# Sheet-new.net
KiCad netlist of a schematic drawn in Altium Designer
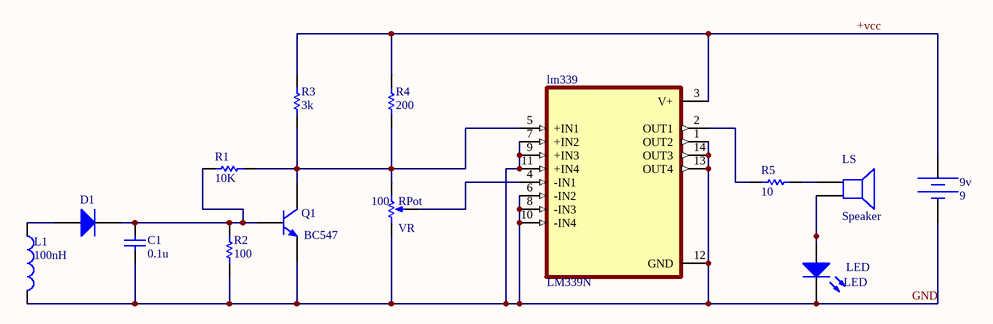
[diagram p0: Sheet-new.SchDoc]

(export (version "E")
  (design (tool "Eeschema 10.0.6"))
  (components
    (comp (ref "9v")
      (value "Constant Voltage Source")
      (footprint "MHDR1X2")
      (fields (field (name "DC MAGNITUDE") "9"))
      (libsource (lib "Simulation Generic Components") (part "Battery"))
    )
    (comp (ref "C1")
      (value "0.1u")
      (footprint "CAPR5-4X5")
      (description "Capacitor")
      (libsource (lib "Simulation Generic Components") (part "Capacitor"))
    )
    (comp (ref "D1")
      (value "Diode")
      (footprint "DIODE-0.4")
      (libsource (lib "Simulation Generic Components") (part "Diode"))
    )
    (comp (ref "L1")
      (value "Inductor")
      (footprint "HDR1X2")
      (fields (field (name "L1") "100nH"))
      (libsource (lib "Simulation Generic Components") (part "Inductor"))
    )
    (comp (ref "LED")
      (value "LED")
      (footprint "HDR1X2")
      (description "Light-Emitting Diode")
      (libsource (lib "Simulation Generic Components") (part "LED"))
    )
    (comp (ref "lm339")
      (value "LM339N")
      (footprint "DIP794W45P254L1969H508Q14")
      (libsource (lib "LM339N") (part "LM339N"))
    )
    (comp (ref "LS")
      (value "Speaker")
      (footprint "PIN2")
      (description "Loudspeaker")
      (fields (field (name "PUBLISHER") "Altium Limited"))
      (libsource (lib "Miscellaneous Devices") (part "Speaker"))
    )
    (comp (ref "Q1")
      (value "BC547")
      (footprint "TO92")
      (description "Bipolar NPN 3 Pins Transistor Modified Version of the Gummel-Poon Model")
      (libsource (lib "Simulation Generic Components") (part "BJT NPN_MGP"))
    )
    (comp (ref "R1")
      (value "10K")
      (footprint "AXIAL-0.4")
      (description "Resistor")
      (libsource (lib "Simulation Generic Components") (part "Resistor"))
    )
    (comp (ref "R2")
      (value "100")
      (footprint "AXIAL-0.4")
      (description "Resistor")
      (libsource (lib "Simulation Generic Components") (part "Resistor"))
    )
    (comp (ref "R3")
      (value "3k")
      (footprint "AXIAL-0.4")
      (description "Resistor")
      (libsource (lib "Simulation Generic Components") (part "Resistor"))
    )
    (comp (ref "R4")
      (value "200")
      (footprint "AXIAL-0.4")
      (description "Resistor")
      (libsource (lib "Simulation Generic Components") (part "Resistor"))
    )
    (comp (ref "R5")
      (value "10")
      (footprint "AXIAL-0.4")
      (description "Resistor")
      (libsource (lib "Simulation Generic Components") (part "Resistor"))
    )
    (comp (ref "VR")
      (value "RPot")
      (footprint "VR4")
      (description "Potentiometer")
      (fields (field (name "ALTIUM_VALUE") "100") (field (name "PUBLISHER") "Altium Limited"))
      (libsource (lib "Miscellaneous Devices") (part "RPot"))
    )
  )
  (nets
    (net (code "1") (name "/+vcc") (class "Default")
      (node (ref "9v") (pin "1") (pinfunction "1_1") (pintype "passive"))
      (node (ref "R3") (pin "1") (pinfunction "1_1") (pintype "passive"))
      (node (ref "R4") (pin "1") (pinfunction "1_1") (pintype "passive"))
      (node (ref "lm339") (pin "3") (pinfunction "V+_3") (pintype "power_in"))
    )
    (net (code "2") (name "/GND") (class "Default")
      (node (ref "9v") (pin "2") (pinfunction "2_2") (pintype "passive"))
      (node (ref "C1") (pin "1") (pinfunction "1_1") (pintype "passive"))
      (node (ref "L1") (pin "2") (pinfunction "2_2") (pintype "passive"))
      (node (ref "LED") (pin "2") (pinfunction "K_2") (pintype "passive"))
      (node (ref "Q1") (pin "3") (pinfunction "E_3") (pintype "passive"))
      (node (ref "R2") (pin "2") (pinfunction "2_2") (pintype "passive"))
      (node (ref "VR") (pin "1") (pinfunction "TOP_1") (pintype "passive"))
      (node (ref "lm339") (pin "1") (pinfunction "OUT2_1") (pintype "output"))
      (node (ref "lm339") (pin "10") (pinfunction "-IN4_10") (pintype "input"))
      (node (ref "lm339") (pin "11") (pinfunction "+IN4_11") (pintype "input"))
      (node (ref "lm339") (pin "12") (pinfunction "GND_12") (pintype "power_in"))
      (node (ref "lm339") (pin "13") (pinfunction "OUT4_13") (pintype "output"))
      (node (ref "lm339") (pin "14") (pinfunction "OUT3_14") (pintype "output"))
      (node (ref "lm339") (pin "6") (pinfunction "-IN2_6") (pintype "input"))
      (node (ref "lm339") (pin "7") (pinfunction "+IN2_7") (pintype "input"))
      (node (ref "lm339") (pin "8") (pinfunction "-IN3_8") (pintype "input"))
      (node (ref "lm339") (pin "9") (pinfunction "+IN3_9") (pintype "input"))
    )
    (net (code "3") (name "Net-(D1-A)") (class "Default")
      (node (ref "D1") (pin "1") (pinfunction "A_1") (pintype "passive"))
      (node (ref "L1") (pin "1") (pinfunction "1_1") (pintype "passive"))
    )
    (net (code "4") (name "Net-(D1-K)") (class "Default")
      (node (ref "C1") (pin "2") (pinfunction "2_2") (pintype "passive"))
      (node (ref "D1") (pin "2") (pinfunction "K_2") (pintype "passive"))
      (node (ref "Q1") (pin "2") (pinfunction "B_2") (pintype "passive"))
      (node (ref "R1") (pin "1") (pinfunction "1_1") (pintype "passive"))
      (node (ref "R2") (pin "1") (pinfunction "1_1") (pintype "passive"))
    )
    (net (code "5") (name "Net-(LED-A)") (class "Default")
      (node (ref "LED") (pin "1") (pinfunction "A_1") (pintype "passive"))
      (node (ref "LS") (pin "2") (pinfunction "2_2") (pintype "passive"))
    )
    (net (code "6") (name "Net-(LS-Pad1)") (class "Default")
      (node (ref "LS") (pin "1") (pinfunction "1_1") (pintype "passive"))
      (node (ref "R5") (pin "2") (pinfunction "2_2") (pintype "passive"))
    )
    (net (code "7") (name "Net-(Q1-C)") (class "Default")
      (node (ref "Q1") (pin "1") (pinfunction "C_1") (pintype "passive"))
      (node (ref "R1") (pin "2") (pinfunction "2_2") (pintype "passive"))
      (node (ref "R3") (pin "2") (pinfunction "2_2") (pintype "passive"))
      (node (ref "R4") (pin "2") (pinfunction "2_2") (pintype "passive"))
      (node (ref "VR") (pin "2") (pinfunction "BOT_2") (pintype "passive"))
      (node (ref "lm339") (pin "5") (pinfunction "+IN1_5") (pintype "input"))
    )
    (net (code "8") (name "Net-(VR-TAP)") (class "Default")
      (node (ref "VR") (pin "3") (pinfunction "TAP_3") (pintype "passive"))
      (node (ref "lm339") (pin "4") (pinfunction "-IN1_4") (pintype "input"))
    )
    (net (code "9") (name "Net-(lm339-OUT1)") (class "Default")
      (node (ref "R5") (pin "1") (pinfunction "1_1") (pintype "passive"))
      (node (ref "lm339") (pin "2") (pinfunction "OUT1_2") (pintype "output"))
    )
  )
)
